# attiny-devboard.net
KiCad netlist of a schematic drawn in EAGLE
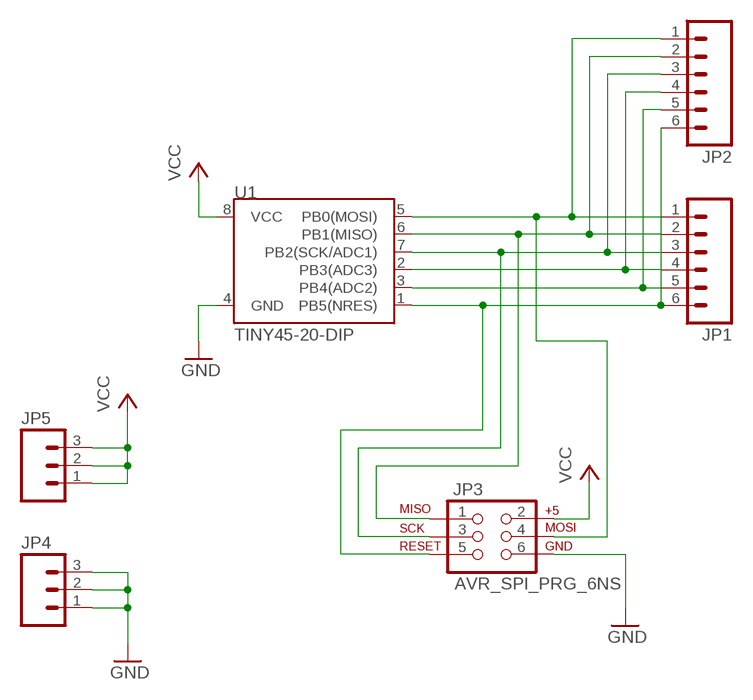
[diagram p0: schematic, sheet 1]

(export (version "E")
  (design (tool "Eeschema 10.0.6"))
  (components
    (comp (ref "JP1")
      (value "M06LOCK")
      (footprint "eagle-import:1X06_LOCK")
      (libsource (lib "eagle-import") (part "M06LOCK"))
    )
    (comp (ref "JP2")
      (value "M06LOCK")
      (footprint "eagle-import:1X06_LOCK")
      (libsource (lib "eagle-import") (part "M06LOCK"))
    )
    (comp (ref "JP3")
      (value "AVR_SPI_PRG_6NS")
      (footprint "eagle-import:2X3-NS")
      (libsource (lib "eagle-import") (part "AVR_SPI_PRG_6NS"))
    )
    (comp (ref "JP4")
      (value "M03LOCK")
      (footprint "eagle-import:1X03_LOCK")
      (libsource (lib "eagle-import") (part "M03LOCK"))
    )
    (comp (ref "JP5")
      (value "M03LOCK")
      (footprint "eagle-import:1X03_LOCK")
      (libsource (lib "eagle-import") (part "M03LOCK"))
    )
    (comp (ref "U1")
      (value "TINY45-20-DIP")
      (footprint "eagle-import:DIP08")
      (libsource (lib "eagle-import") (part "ATTINY45TINY45-20-DIP"))
    )
  )
  (nets
    (net (code "1") (name "GND") (class "Default")
      (node (ref "JP3") (pin "6") (pinfunction "6_6") (pintype "passive"))
      (node (ref "JP4") (pin "1") (pinfunction "1_1") (pintype "passive"))
      (node (ref "JP4") (pin "2") (pinfunction "2_2") (pintype "passive"))
      (node (ref "JP4") (pin "3") (pinfunction "3_3") (pintype "passive"))
      (node (ref "U1") (pin "4") (pinfunction "GND_4") (pintype "bidirectional"))
    )
    (net (code "2") (name "Net-(U1-PB0(MOSI))") (class "Default")
      (node (ref "JP1") (pin "1") (pinfunction "1_1") (pintype "passive"))
      (node (ref "JP2") (pin "1") (pinfunction "1_1") (pintype "passive"))
      (node (ref "JP3") (pin "4") (pinfunction "4_4") (pintype "passive"))
      (node (ref "U1") (pin "5") (pinfunction "PB0(MOSI)_5") (pintype "bidirectional"))
    )
    (net (code "3") (name "Net-(U1-PB1(MISO))") (class "Default")
      (node (ref "JP1") (pin "2") (pinfunction "2_2") (pintype "passive"))
      (node (ref "JP2") (pin "2") (pinfunction "2_2") (pintype "passive"))
      (node (ref "JP3") (pin "1") (pinfunction "1_1") (pintype "passive"))
      (node (ref "U1") (pin "6") (pinfunction "PB1(MISO)_6") (pintype "bidirectional"))
    )
    (net (code "4") (name "Net-(U1-PB2(SCK{slash}ADC1))") (class "Default")
      (node (ref "JP1") (pin "3") (pinfunction "3_3") (pintype "passive"))
      (node (ref "JP2") (pin "3") (pinfunction "3_3") (pintype "passive"))
      (node (ref "JP3") (pin "3") (pinfunction "3_3") (pintype "passive"))
      (node (ref "U1") (pin "7") (pinfunction "PB2(SCK/ADC1)_7") (pintype "bidirectional"))
    )
    (net (code "5") (name "Net-(U1-PB3(ADC3))") (class "Default")
      (node (ref "JP1") (pin "4") (pinfunction "4_4") (pintype "passive"))
      (node (ref "JP2") (pin "4") (pinfunction "4_4") (pintype "passive"))
      (node (ref "U1") (pin "2") (pinfunction "PB3(ADC3)_2") (pintype "bidirectional"))
    )
    (net (code "6") (name "Net-(U1-PB4(ADC2))") (class "Default")
      (node (ref "JP1") (pin "5") (pinfunction "5_5") (pintype "passive"))
      (node (ref "JP2") (pin "5") (pinfunction "5_5") (pintype "passive"))
      (node (ref "U1") (pin "3") (pinfunction "PB4(ADC2)_3") (pintype "bidirectional"))
    )
    (net (code "7") (name "Net-(U1-PB5(NRES))") (class "Default")
      (node (ref "JP1") (pin "6") (pinfunction "6_6") (pintype "passive"))
      (node (ref "JP2") (pin "6") (pinfunction "6_6") (pintype "passive"))
      (node (ref "JP3") (pin "5") (pinfunction "5_5") (pintype "passive"))
      (node (ref "U1") (pin "1") (pinfunction "PB5(NRES)_1") (pintype "bidirectional"))
    )
    (net (code "8") (name "VCC") (class "Default")
      (node (ref "JP3") (pin "2") (pinfunction "2_2") (pintype "passive"))
      (node (ref "JP5") (pin "1") (pinfunction "1_1") (pintype "passive"))
      (node (ref "JP5") (pin "2") (pinfunction "2_2") (pintype "passive"))
      (node (ref "JP5") (pin "3") (pinfunction "3_3") (pintype "passive"))
      (node (ref "U1") (pin "8") (pinfunction "VCC_8") (pintype "bidirectional"))
    )
  )
)
